# Sheet1.net
KiCad netlist of a schematic drawn in Altium Designer
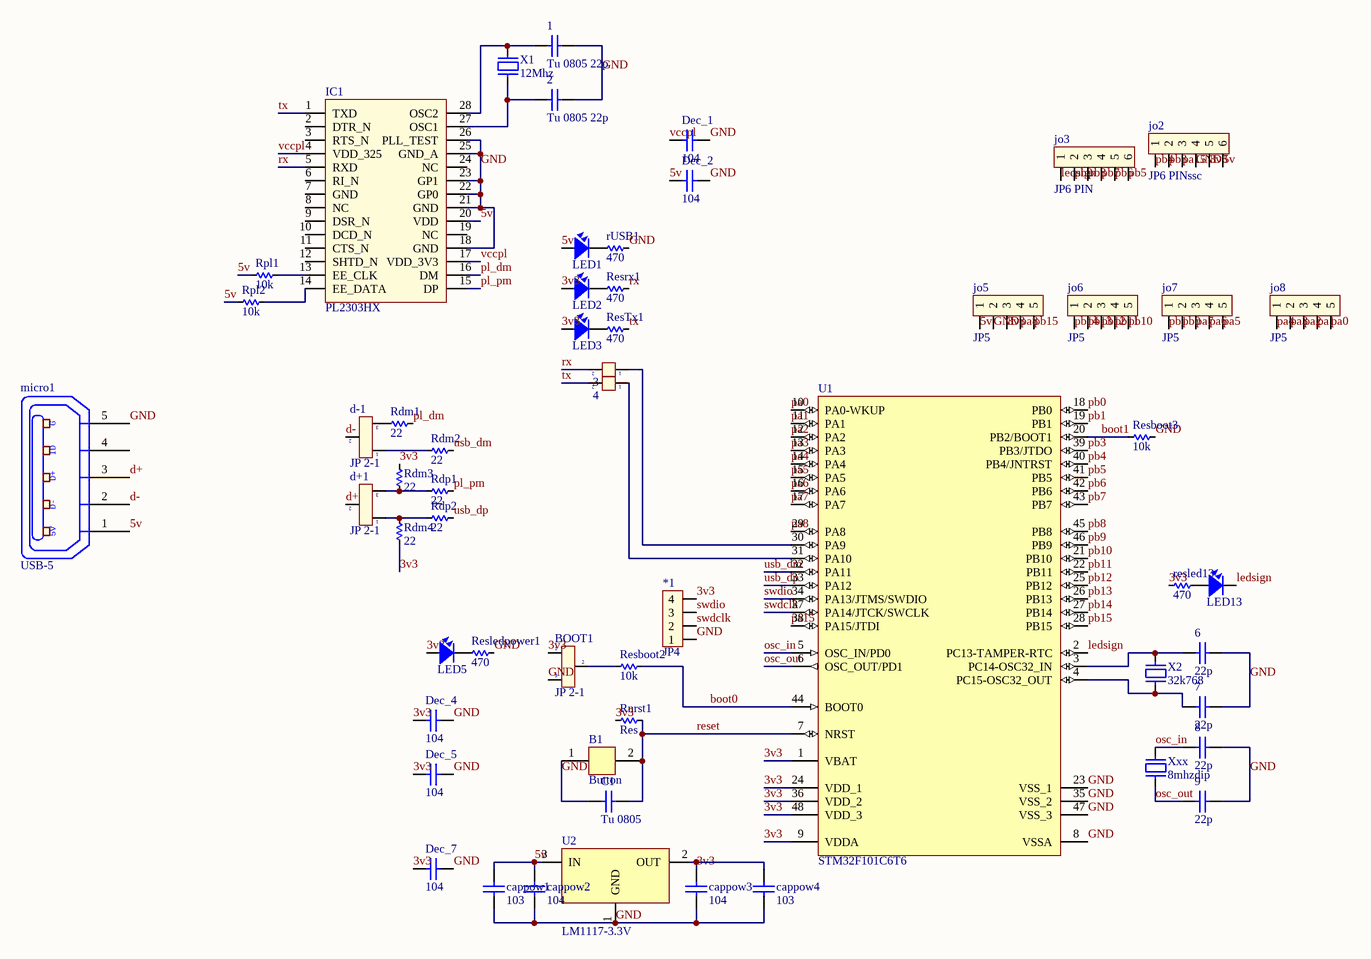
[diagram p0: Sheet1.SchDoc]

(export (version "E")
  (design (tool "Eeschema 10.0.6"))
  (components
    (comp (ref "*1")
      (value "JP4")
      (footprint "JP4")
      (libsource (lib "MH_THU VIEN CHUAN 12-03-2015") (part "JP4"))
    )
    (comp (ref "1")
      (value "Tu 0805 22p")
      (footprint "Tu 0805")
      (libsource (lib "MH_THU VIEN CHUAN 12-03-2015") (part "CAP 0805"))
    )
    (comp (ref "2")
      (value "Tu 0805 22p")
      (footprint "Tu 0805")
      (libsource (lib "MH_THU VIEN CHUAN 12-03-2015") (part "CAP 0805"))
    )
    (comp (ref "3")
      (value "Jumper 2")
      (footprint "JP2")
      (libsource (lib "MH_THU VIEN CHUAN 12-03-2015") (part "JP 2"))
    )
    (comp (ref "4")
      (value "Jumper 2")
      (footprint "JP2")
      (libsource (lib "MH_THU VIEN CHUAN 12-03-2015") (part "JP 2"))
    )
    (comp (ref "6")
      (value "22p")
      (footprint "Tu 0805")
      (libsource (lib "MH_THU VIEN CHUAN 12-03-2015") (part "CAP 0805"))
    )
    (comp (ref "7")
      (value "22p")
      (footprint "Tu 0805")
      (libsource (lib "MH_THU VIEN CHUAN 12-03-2015") (part "CAP 0805"))
    )
    (comp (ref "8")
      (value "22p")
      (footprint "Tu 0805")
      (libsource (lib "MH_THU VIEN CHUAN 12-03-2015") (part "CAP 0805"))
    )
    (comp (ref "9")
      (value "22p")
      (footprint "Tu 0805")
      (libsource (lib "MH_THU VIEN CHUAN 12-03-2015") (part "CAP 0805"))
    )
    (comp (ref "B1")
      (value "Button")
      (footprint "Button 2 Pin")
      (description "Button 2 pin")
      (libsource (lib "MH_THU VIEN CHUAN 12-03-2015") (part "Button 2 Pin"))
    )
    (comp (ref "BOOT1")
      (value "JP 2-1")
      (footprint "JP3")
      (description "Jumper 2-1")
      (libsource (lib "") (part "JP 2-1_1_1"))
    )
    (comp (ref "C1")
      (value "Tu 0805")
      (footprint "Tu 0805")
      (libsource (lib "MH_THU VIEN CHUAN 12-03-2015") (part "CAP 0805"))
    )
    (comp (ref "cappow1")
      (value "103")
      (footprint "Tu 0805")
      (libsource (lib "MH_THU VIEN CHUAN 12-03-2015") (part "CAP 0805"))
    )
    (comp (ref "cappow2")
      (value "104")
      (footprint "Tu 0805")
      (libsource (lib "MH_THU VIEN CHUAN 12-03-2015") (part "CAP 0805"))
    )
    (comp (ref "cappow3")
      (value "104")
      (footprint "Tu 0805")
      (libsource (lib "MH_THU VIEN CHUAN 12-03-2015") (part "CAP 0805"))
    )
    (comp (ref "cappow4")
      (value "103")
      (footprint "Tu 0805")
      (libsource (lib "MH_THU VIEN CHUAN 12-03-2015") (part "CAP 0805"))
    )
    (comp (ref "d+1")
      (value "JP 2-1")
      (footprint "JP3")
      (description "Jumper 2-1")
      (libsource (lib "MH_THU VIEN CHUAN 12-03-2015") (part "JP 2-1_1"))
    )
    (comp (ref "d-1")
      (value "JP 2-1")
      (footprint "JP3")
      (description "Jumper 2-1")
      (libsource (lib "MH_THU VIEN CHUAN 12-03-2015") (part "JP 2-1_1"))
    )
    (comp (ref "Dec_1")
      (value "104")
      (footprint "Tu 0805")
      (libsource (lib "MH_THU VIEN CHUAN 12-03-2015") (part "CAP 0805"))
    )
    (comp (ref "Dec_2")
      (value "104")
      (footprint "Tu 0805")
      (libsource (lib "MH_THU VIEN CHUAN 12-03-2015") (part "CAP 0805"))
    )
    (comp (ref "Dec_4")
      (value "104")
      (footprint "Tu 0805")
      (libsource (lib "MH_THU VIEN CHUAN 12-03-2015") (part "CAP 0805"))
    )
    (comp (ref "Dec_5")
      (value "104")
      (footprint "Tu 0805")
      (libsource (lib "MH_THU VIEN CHUAN 12-03-2015") (part "CAP 0805"))
    )
    (comp (ref "Dec_7")
      (value "104")
      (footprint "Tu 0805")
      (libsource (lib "MH_THU VIEN CHUAN 12-03-2015") (part "CAP 0805"))
    )
    (comp (ref "IC1")
      (value "PL2303HX")
      (footprint "SO-G28/C6.8")
      (description "USB - RS232 Converter")
      (libsource (lib "syhaunguyen") (part "PL2303HX"))
    )
    (comp (ref "jo2")
      (value "JP6 PINssc")
      (footprint "JP6")
      (description "JP6 PIN")
      (libsource (lib "MH_THU VIEN CHUAN 12-03-2015") (part "JP6"))
    )
    (comp (ref "jo3")
      (value "JP6 PIN")
      (footprint "JP6")
      (libsource (lib "MH_THU VIEN CHUAN 12-03-2015") (part "JP6"))
    )
    (comp (ref "jo5")
      (value "JP5")
      (footprint "JP5")
      (libsource (lib "MH_THU VIEN CHUAN 12-03-2015") (part "JP5"))
    )
    (comp (ref "jo6")
      (value "JP5")
      (footprint "JP5")
      (libsource (lib "MH_THU VIEN CHUAN 12-03-2015") (part "JP5"))
    )
    (comp (ref "jo7")
      (value "JP5")
      (footprint "JP5")
      (libsource (lib "MH_THU VIEN CHUAN 12-03-2015") (part "JP5"))
    )
    (comp (ref "jo8")
      (value "JP5")
      (footprint "JP5")
      (libsource (lib "MH_THU VIEN CHUAN 12-03-2015") (part "JP5"))
    )
    (comp (ref "LED1")
      (value "LED SMD")
      (footprint "SM-LED-0805-Blue")
      (libsource (lib "syhaunguyen") (part "LED-SMD-0805"))
    )
    (comp (ref "LED2")
      (value "LED SMD")
      (footprint "SM-LED-0805-Blue")
      (libsource (lib "syhaunguyen") (part "LED-SMD-0805"))
    )
    (comp (ref "LED3")
      (value "LED SMD")
      (footprint "SM-LED-0805-Blue")
      (libsource (lib "syhaunguyen") (part "LED-SMD-0805"))
    )
    (comp (ref "LED5")
      (value "LED SMD")
      (footprint "SM-LED-0805-Blue")
      (libsource (lib "syhaunguyen") (part "LED-SMD-0805"))
    )
    (comp (ref "LED13")
      (value "LED SMD")
      (footprint "SM-LED-0805-Blue")
      (libsource (lib "syhaunguyen") (part "LED-SMD-0805"))
    )
    (comp (ref "micro1")
      (value "USB-5")
      (footprint "USB-M1")
      (fields
        (field (name "MANUFACTURER") "FCI")
        (field (name "MANUFACTURER PART NUMBER") "10118193-0001LF")
        (field (name ".CREATOR") "MM")
        (field (name ".CHECKED PCB") "RF")
        (field (name ".CHECKED SCH") "MM")
      )
      (libsource (lib "LIBRARY") (part "USB-5"))
    )
    (comp (ref "Rdm1")
      (value "22")
      (footprint "RES-SMD-0805")
      (description "Resistor")
      (fields
        (field (name "MANUFACTURER") "Generic Components")
        (field (name "PUBLISHER") "Altium Hobart Technology Centre")
      )
      (libsource (lib "LIBRARY") (part "Res-SMD"))
    )
    (comp (ref "Rdm2")
      (value "22")
      (footprint "RES-SMD-0805")
      (description "Resistor")
      (fields
        (field (name "MANUFACTURER") "Generic Components")
        (field (name "PUBLISHER") "Altium Hobart Technology Centre")
      )
      (libsource (lib "LIBRARY") (part "Res-SMD"))
    )
    (comp (ref "Rdm3")
      (value "22")
      (footprint "RES-SMD-0805")
      (description "Resistor")
      (fields
        (field (name "MANUFACTURER") "Generic Components")
        (field (name "PUBLISHER") "Altium Hobart Technology Centre")
      )
      (libsource (lib "LIBRARY") (part "Res-SMD"))
    )
    (comp (ref "Rdm4")
      (value "22")
      (footprint "RES-SMD-0805")
      (description "Resistor")
      (fields
        (field (name "MANUFACTURER") "Generic Components")
        (field (name "PUBLISHER") "Altium Hobart Technology Centre")
      )
      (libsource (lib "LIBRARY") (part "Res-SMD"))
    )
    (comp (ref "Rdp1")
      (value "22")
      (footprint "RES-SMD-0805")
      (description "Resistor")
      (fields
        (field (name "MANUFACTURER") "Generic Components")
        (field (name "PUBLISHER") "Altium Hobart Technology Centre")
      )
      (libsource (lib "LIBRARY") (part "Res-SMD"))
    )
    (comp (ref "Rdp2")
      (value "22")
      (footprint "RES-SMD-0805")
      (description "Resistor")
      (fields
        (field (name "MANUFACTURER") "Generic Components")
        (field (name "PUBLISHER") "Altium Hobart Technology Centre")
      )
      (libsource (lib "LIBRARY") (part "Res-SMD"))
    )
    (comp (ref "Resboot2")
      (value "10k")
      (footprint "RES-SMD-0805")
      (description "Resistor")
      (fields
        (field (name "MANUFACTURER") "Generic Components")
        (field (name "PUBLISHER") "Altium Hobart Technology Centre")
      )
      (libsource (lib "LIBRARY") (part "Res-SMD"))
    )
    (comp (ref "Resboot3")
      (value "10k")
      (footprint "RES-SMD-0805")
      (description "Resistor")
      (fields
        (field (name "MANUFACTURER") "Generic Components")
        (field (name "PUBLISHER") "Altium Hobart Technology Centre")
      )
      (libsource (lib "LIBRARY") (part "Res-SMD"))
    )
    (comp (ref "resled13")
      (value "470")
      (footprint "RES-SMD-0805")
      (description "Resistor")
      (fields
        (field (name "MANUFACTURER") "Generic Components")
        (field (name "PUBLISHER") "Altium Hobart Technology Centre")
      )
      (libsource (lib "LIBRARY") (part "Res-SMD"))
    )
    (comp (ref "Resledpower1")
      (value "470")
      (footprint "RES-SMD-0805")
      (description "Resistor")
      (fields
        (field (name "MANUFACTURER") "Generic Components")
        (field (name "PUBLISHER") "Altium Hobart Technology Centre")
      )
      (libsource (lib "LIBRARY") (part "Res-SMD"))
    )
    (comp (ref "Resrx1")
      (value "470")
      (footprint "RES-SMD-0805")
      (description "Resistor")
      (fields
        (field (name "MANUFACTURER") "Generic Components")
        (field (name "PUBLISHER") "Altium Hobart Technology Centre")
      )
      (libsource (lib "LIBRARY") (part "Res-SMD"))
    )
    (comp (ref "ResTx1")
      (value "470")
      (footprint "RES-SMD-0805")
      (description "Resistor")
      (fields
        (field (name "MANUFACTURER") "Generic Components")
        (field (name "PUBLISHER") "Altium Hobart Technology Centre")
      )
      (libsource (lib "LIBRARY") (part "Res-SMD"))
    )
    (comp (ref "Rnrst1")
      (value "Res")
      (footprint "RES-SMD-0805")
      (description "Resistor")
      (fields
        (field (name "MANUFACTURER") "Generic Components")
        (field (name "PUBLISHER") "Altium Hobart Technology Centre")
      )
      (libsource (lib "LIBRARY") (part "Res-SMD"))
    )
    (comp (ref "Rpl1")
      (value "10k")
      (footprint "RES-SMD-0805")
      (description "Resistor")
      (fields
        (field (name "MANUFACTURER") "Generic Components")
        (field (name "PUBLISHER") "Altium Hobart Technology Centre")
      )
      (libsource (lib "LIBRARY") (part "Res-SMD"))
    )
    (comp (ref "Rpl2")
      (value "10k")
      (footprint "RES-SMD-0805")
      (description "Resistor")
      (fields
        (field (name "MANUFACTURER") "Generic Components")
        (field (name "PUBLISHER") "Altium Hobart Technology Centre")
      )
      (libsource (lib "LIBRARY") (part "Res-SMD"))
    )
    (comp (ref "rUSB1")
      (value "470")
      (footprint "RES-SMD-0805")
      (description "Resistor")
      (fields
        (field (name "MANUFACTURER") "Generic Components")
        (field (name "PUBLISHER") "Altium Hobart Technology Centre")
      )
      (libsource (lib "LIBRARY") (part "Res-SMD"))
    )
    (comp (ref "U1")
      (value "STM32F101C6T6")
      (footprint "TQFP48")
      (description "STM32 ARM-based 32-bit MCU with 32 Kbytes Flash, 48-pin LQFP, Industrial Temperature")
      (fields (field (name "PUBLISHER") "Altium Limited"))
      (libsource (lib "LIBRARY") (part "STM32F101C6T6"))
    )
    (comp (ref "U2")
      (value "LM1117-3.3V")
      (footprint "LM1117-SOP")
      (description "800mA Low-Dropout Linear Regulator")
      (fields (field (name "CREATOR") "Nguyen Ba Bien"))
      (libsource (lib "MH_THU VIEN CHUAN 12-03-2015") (part "LM1117"))
    )
    (comp (ref "X1")
      (value "12Mhz")
      (footprint "XT2-SMD")
      (description "Crystal, 32.768 KHz, -40 to 85 degC, 3.2 x 1.5 x 0.9 mm SMD")
      (libsource (lib "LIBRARY") (part "XT2"))
    )
    (comp (ref "X2")
      (value "32k768")
      (footprint "XT32k")
      (description "Crystal, 32.768 KHz, -40 to 85 degC, 3.2 x 1.5 x 0.9 mm SMD")
      (libsource (lib "") (part "XT2_1"))
    )
    (comp (ref "Xxx")
      (value "8mhzdip")
      (footprint "XT2")
      (description "Crystal For all Crystal 2pin.")
      (libsource (lib "syhaunguyen") (part "XT2"))
    )
  )
  (nets
    (net (code "1") (name "/3v3") (class "Default")
      (node (ref "*1") (pin "4") (pinfunction "4_4") (pintype "passive"))
      (node (ref "BOOT1") (pin "1") (pinfunction "1_1") (pintype "passive"))
      (node (ref "Dec_4") (pin "1") (pinfunction "1_1") (pintype "passive"))
      (node (ref "Dec_5") (pin "1") (pinfunction "1_1") (pintype "passive"))
      (node (ref "Dec_7") (pin "1") (pinfunction "1_1") (pintype "passive"))
      (node (ref "LED2") (pin "1") (pinfunction "1_1") (pintype "passive"))
      (node (ref "LED3") (pin "1") (pinfunction "1_1") (pintype "passive"))
      (node (ref "LED5") (pin "1") (pinfunction "1_1") (pintype "passive"))
      (node (ref "Rdm3") (pin "1") (pinfunction "1_1") (pintype "passive"))
      (node (ref "Rdm4") (pin "2") (pinfunction "2_2") (pintype "passive"))
      (node (ref "Rnrst1") (pin "2") (pinfunction "2_2") (pintype "passive"))
      (node (ref "U1") (pin "1") (pinfunction "VBAT_1") (pintype "power_in"))
      (node (ref "U1") (pin "24") (pinfunction "VDD_1_24") (pintype "power_in"))
      (node (ref "U1") (pin "36") (pinfunction "VDD_2_36") (pintype "power_in"))
      (node (ref "U1") (pin "48") (pinfunction "VDD_3_48") (pintype "power_in"))
      (node (ref "U1") (pin "9") (pinfunction "VDDA_9") (pintype "power_in"))
      (node (ref "U2") (pin "2") (pinfunction "OUT_2") (pintype "passive"))
      (node (ref "cappow3") (pin "2") (pinfunction "2_2") (pintype "passive"))
      (node (ref "cappow4") (pin "2") (pinfunction "2_2") (pintype "passive"))
      (node (ref "jo2") (pin "5") (pinfunction "5_5") (pintype "passive"))
      (node (ref "jo5") (pin "3") (pinfunction "3_3") (pintype "passive"))
      (node (ref "resled13") (pin "2") (pinfunction "2_2") (pintype "passive"))
    )
    (net (code "2") (name "/5v") (class "Default")
      (node (ref "Dec_2") (pin "1") (pinfunction "1_1") (pintype "passive"))
      (node (ref "IC1") (pin "20") (pinfunction "VDD_20") (pintype "passive"))
      (node (ref "LED1") (pin "1") (pinfunction "1_1") (pintype "passive"))
      (node (ref "Rpl1") (pin "2") (pinfunction "2_2") (pintype "passive"))
      (node (ref "Rpl2") (pin "2") (pinfunction "2_2") (pintype "passive"))
      (node (ref "U2") (pin "3") (pinfunction "IN_3") (pintype "passive"))
      (node (ref "cappow1") (pin "2") (pinfunction "2_2") (pintype "passive"))
      (node (ref "cappow2") (pin "2") (pinfunction "2_2") (pintype "passive"))
      (node (ref "jo2") (pin "6") (pinfunction "6_6") (pintype "passive"))
      (node (ref "jo5") (pin "1") (pinfunction "1_1") (pintype "passive"))
      (node (ref "micro1") (pin "1") (pinfunction "P1_1") (pintype "passive"))
    )
    (net (code "3") (name "/GND") (class "Default")
      (node (ref "*1") (pin "1") (pinfunction "1_1") (pintype "passive"))
      (node (ref "1") (pin "2") (pinfunction "2_2") (pintype "passive"))
      (node (ref "2") (pin "2") (pinfunction "2_2") (pintype "passive"))
      (node (ref "6") (pin "2") (pinfunction "2_2") (pintype "passive"))
      (node (ref "7") (pin "2") (pinfunction "2_2") (pintype "passive"))
      (node (ref "8") (pin "2") (pinfunction "2_2") (pintype "passive"))
      (node (ref "9") (pin "2") (pinfunction "2_2") (pintype "passive"))
      (node (ref "B1") (pin "1") (pinfunction "1_1") (pintype "passive"))
      (node (ref "BOOT1") (pin "3") (pinfunction "3_3") (pintype "passive"))
      (node (ref "C1") (pin "2") (pinfunction "2_2") (pintype "passive"))
      (node (ref "Dec_1") (pin "1") (pinfunction "1_1") (pintype "passive"))
      (node (ref "Dec_2") (pin "2") (pinfunction "2_2") (pintype "passive"))
      (node (ref "Dec_4") (pin "2") (pinfunction "2_2") (pintype "passive"))
      (node (ref "Dec_5") (pin "2") (pinfunction "2_2") (pintype "passive"))
      (node (ref "Dec_7") (pin "2") (pinfunction "2_2") (pintype "passive"))
      (node (ref "IC1") (pin "18") (pinfunction "GND_18") (pintype "passive"))
      (node (ref "IC1") (pin "21") (pinfunction "GND_21") (pintype "passive"))
      (node (ref "IC1") (pin "22") (pinfunction "GP0_22") (pintype "passive"))
      (node (ref "IC1") (pin "23") (pinfunction "GP1_23") (pintype "passive"))
      (node (ref "IC1") (pin "25") (pinfunction "GND_A_25") (pintype "passive"))
      (node (ref "IC1") (pin "26") (pinfunction "PLL_TEST_26") (pintype "passive"))
      (node (ref "Resboot3") (pin "1") (pinfunction "1_1") (pintype "passive"))
      (node (ref "Resledpower1") (pin "1") (pinfunction "1_1") (pintype "passive"))
      (node (ref "U1") (pin "23") (pinfunction "VSS_1_23") (pintype "power_in"))
      (node (ref "U1") (pin "35") (pinfunction "VSS_2_35") (pintype "power_in"))
      (node (ref "U1") (pin "47") (pinfunction "VSS_3_47") (pintype "power_in"))
      (node (ref "U1") (pin "8") (pinfunction "VSSA_8") (pintype "power_in"))
      (node (ref "U2") (pin "1") (pinfunction "GND_1") (pintype "passive"))
      (node (ref "cappow1") (pin "1") (pinfunction "1_1") (pintype "passive"))
      (node (ref "cappow2") (pin "1") (pinfunction "1_1") (pintype "passive"))
      (node (ref "cappow3") (pin "1") (pinfunction "1_1") (pintype "passive"))
      (node (ref "cappow4") (pin "1") (pinfunction "1_1") (pintype "passive"))
      (node (ref "jo2") (pin "4") (pinfunction "4_4") (pintype "passive"))
      (node (ref "jo5") (pin "2") (pinfunction "2_2") (pintype "passive"))
      (node (ref "micro1") (pin "5") (pinfunction "P5_5") (pintype "passive"))
      (node (ref "rUSB1") (pin "1") (pinfunction "1_1") (pintype "passive"))
    )
    (net (code "4") (name "/boot0") (class "Default")
      (node (ref "Resboot2") (pin "1") (pinfunction "1_1") (pintype "passive"))
      (node (ref "U1") (pin "44") (pinfunction "BOOT0_44") (pintype "input"))
    )
    (net (code "5") (name "/boot1") (class "Default")
      (node (ref "Resboot3") (pin "2") (pinfunction "2_2") (pintype "passive"))
      (node (ref "U1") (pin "20") (pinfunction "PB2/BOOT1_20") (pintype "bidirectional"))
    )
    (net (code "6") (name "/d+") (class "Default")
      (node (ref "d+1") (pin "2") (pinfunction "2_2") (pintype "passive"))
      (node (ref "micro1") (pin "3") (pinfunction "P3_3") (pintype "passive"))
    )
    (net (code "7") (name "/d-") (class "Default")
      (node (ref "d-1") (pin "2") (pinfunction "2_2") (pintype "passive"))
      (node (ref "micro1") (pin "2") (pinfunction "P2_2") (pintype "passive"))
    )
    (net (code "8") (name "/ledsign") (class "Default")
      (node (ref "LED13") (pin "2") (pinfunction "2_2") (pintype "passive"))
      (node (ref "U1") (pin "2") (pinfunction "PC13-TAMPER-RTC_2") (pintype "bidirectional"))
      (node (ref "jo3") (pin "1") (pinfunction "1_1") (pintype "passive"))
    )
    (net (code "9") (name "/osc_in") (class "Default")
      (node (ref "8") (pin "1") (pinfunction "1_1") (pintype "passive"))
      (node (ref "U1") (pin "5") (pinfunction "OSC_IN/PD0_5") (pintype "input"))
      (node (ref "Xxx") (pin "2") (pinfunction "2_2") (pintype "passive"))
    )
    (net (code "10") (name "/osc_out") (class "Default")
      (node (ref "9") (pin "1") (pinfunction "1_1") (pintype "passive"))
      (node (ref "U1") (pin "6") (pinfunction "OSC_OUT/PD1_6") (pintype "output"))
      (node (ref "Xxx") (pin "1") (pinfunction "1_1") (pintype "passive"))
    )
    (net (code "11") (name "/pa0") (class "Default")
      (node (ref "U1") (pin "10") (pinfunction "PA0-WKUP_10") (pintype "bidirectional"))
      (node (ref "jo8") (pin "5") (pinfunction "5_5") (pintype "passive"))
    )
    (net (code "12") (name "/pa1") (class "Default")
      (node (ref "U1") (pin "11") (pinfunction "PA1_11") (pintype "bidirectional"))
      (node (ref "jo8") (pin "4") (pinfunction "4_4") (pintype "passive"))
    )
    (net (code "13") (name "/pa2") (class "Default")
      (node (ref "U1") (pin "12") (pinfunction "PA2_12") (pintype "bidirectional"))
      (node (ref "jo8") (pin "3") (pinfunction "3_3") (pintype "passive"))
    )
    (net (code "14") (name "/pa3") (class "Default")
      (node (ref "U1") (pin "13") (pinfunction "PA3_13") (pintype "bidirectional"))
      (node (ref "jo8") (pin "2") (pinfunction "2_2") (pintype "passive"))
    )
    (net (code "15") (name "/pa4") (class "Default")
      (node (ref "U1") (pin "14") (pinfunction "PA4_14") (pintype "bidirectional"))
      (node (ref "jo8") (pin "1") (pinfunction "1_1") (pintype "passive"))
    )
    (net (code "16") (name "/pa5") (class "Default")
      (node (ref "U1") (pin "15") (pinfunction "PA5_15") (pintype "bidirectional"))
      (node (ref "jo7") (pin "5") (pinfunction "5_5") (pintype "passive"))
    )
    (net (code "17") (name "/pa6") (class "Default")
      (node (ref "U1") (pin "16") (pinfunction "PA6_16") (pintype "bidirectional"))
      (node (ref "jo7") (pin "4") (pinfunction "4_4") (pintype "passive"))
    )
    (net (code "18") (name "/pa7") (class "Default")
      (node (ref "U1") (pin "17") (pinfunction "PA7_17") (pintype "bidirectional"))
      (node (ref "jo7") (pin "3") (pinfunction "3_3") (pintype "passive"))
    )
    (net (code "19") (name "/pa8") (class "Default")
      (node (ref "U1") (pin "29") (pinfunction "PA8_29") (pintype "bidirectional"))
      (node (ref "jo5") (pin "4") (pinfunction "4_4") (pintype "passive"))
    )
    (net (code "20") (name "/pa15") (class "Default")
      (node (ref "U1") (pin "38") (pinfunction "PA15/JTDI_38") (pintype "bidirectional"))
      (node (ref "jo2") (pin "3") (pinfunction "3_3") (pintype "passive"))
    )
    (net (code "21") (name "/pb0") (class "Default")
      (node (ref "U1") (pin "18") (pinfunction "PB0_18") (pintype "bidirectional"))
      (node (ref "jo7") (pin "2") (pinfunction "2_2") (pintype "passive"))
    )
    (net (code "22") (name "/pb1") (class "Default")
      (node (ref "U1") (pin "19") (pinfunction "PB1_19") (pintype "bidirectional"))
      (node (ref "jo7") (pin "1") (pinfunction "1_1") (pintype "passive"))
    )
    (net (code "23") (name "/pb3") (class "Default")
      (node (ref "U1") (pin "39") (pinfunction "PB3/JTDO_39") (pintype "bidirectional"))
      (node (ref "jo2") (pin "2") (pinfunction "2_2") (pintype "passive"))
    )
    (net (code "24") (name "/pb4") (class "Default")
      (node (ref "U1") (pin "40") (pinfunction "PB4/JNTRST_40") (pintype "bidirectional"))
      (node (ref "jo2") (pin "1") (pinfunction "1_1") (pintype "passive"))
    )
    (net (code "25") (name "/pb5") (class "Default")
      (node (ref "U1") (pin "41") (pinfunction "PB5_41") (pintype "bidirectional"))
      (node (ref "jo3") (pin "6") (pinfunction "6_6") (pintype "passive"))
    )
    (net (code "26") (name "/pb6") (class "Default")
      (node (ref "U1") (pin "42") (pinfunction "PB6_42") (pintype "bidirectional"))
      (node (ref "jo3") (pin "5") (pinfunction "5_5") (pintype "passive"))
    )
    (net (code "27") (name "/pb7") (class "Default")
      (node (ref "U1") (pin "43") (pinfunction "PB7_43") (pintype "bidirectional"))
      (node (ref "jo3") (pin "4") (pinfunction "4_4") (pintype "passive"))
    )
    (net (code "28") (name "/pb8") (class "Default")
      (node (ref "U1") (pin "45") (pinfunction "PB8_45") (pintype "bidirectional"))
      (node (ref "jo3") (pin "3") (pinfunction "3_3") (pintype "passive"))
    )
    (net (code "29") (name "/pb9") (class "Default")
      (node (ref "U1") (pin "46") (pinfunction "PB9_46") (pintype "bidirectional"))
      (node (ref "jo3") (pin "2") (pinfunction "2_2") (pintype "passive"))
    )
    (net (code "30") (name "/pb10") (class "Default")
      (node (ref "U1") (pin "21") (pinfunction "PB10_21") (pintype "bidirectional"))
      (node (ref "jo6") (pin "5") (pinfunction "5_5") (pintype "passive"))
    )
    (net (code "31") (name "/pb11") (class "Default")
      (node (ref "U1") (pin "22") (pinfunction "PB11_22") (pintype "bidirectional"))
      (node (ref "jo6") (pin "4") (pinfunction "4_4") (pintype "passive"))
    )
    (net (code "32") (name "/pb12") (class "Default")
      (node (ref "U1") (pin "25") (pinfunction "PB12_25") (pintype "bidirectional"))
      (node (ref "jo6") (pin "3") (pinfunction "3_3") (pintype "passive"))
    )
    (net (code "33") (name "/pb13") (class "Default")
      (node (ref "U1") (pin "26") (pinfunction "PB13_26") (pintype "bidirectional"))
      (node (ref "jo6") (pin "2") (pinfunction "2_2") (pintype "passive"))
    )
    (net (code "34") (name "/pb14") (class "Default")
      (node (ref "U1") (pin "27") (pinfunction "PB14_27") (pintype "bidirectional"))
      (node (ref "jo6") (pin "1") (pinfunction "1_1") (pintype "passive"))
    )
    (net (code "35") (name "/pb15") (class "Default")
      (node (ref "U1") (pin "28") (pinfunction "PB15_28") (pintype "bidirectional"))
      (node (ref "jo5") (pin "5") (pinfunction "5_5") (pintype "passive"))
    )
    (net (code "36") (name "/pl_dm") (class "Default")
      (node (ref "IC1") (pin "16") (pinfunction "DM_16") (pintype "passive"))
      (node (ref "Rdm1") (pin "1") (pinfunction "1_1") (pintype "passive"))
    )
    (net (code "37") (name "/pl_pm") (class "Default")
      (node (ref "IC1") (pin "15") (pinfunction "DP_15") (pintype "passive"))
      (node (ref "Rdp1") (pin "1") (pinfunction "1_1") (pintype "passive"))
    )
    (net (code "38") (name "/reset") (class "Default")
      (node (ref "B1") (pin "2") (pinfunction "2_2") (pintype "passive"))
      (node (ref "C1") (pin "1") (pinfunction "1_1") (pintype "passive"))
      (node (ref "Rnrst1") (pin "1") (pinfunction "1_1") (pintype "passive"))
      (node (ref "U1") (pin "7") (pinfunction "NRST_7") (pintype "bidirectional"))
    )
    (net (code "39") (name "/rx") (class "Default")
      (node (ref "3") (pin "2") (pinfunction "2_2") (pintype "passive"))
      (node (ref "IC1") (pin "5") (pinfunction "RXD_5") (pintype "passive"))
      (node (ref "Resrx1") (pin "1") (pinfunction "1_1") (pintype "passive"))
    )
    (net (code "40") (name "/swdclk") (class "Default")
      (node (ref "*1") (pin "2") (pinfunction "2_2") (pintype "passive"))
      (node (ref "U1") (pin "37") (pinfunction "PA14/JTCK/SWCLK_37") (pintype "bidirectional"))
    )
    (net (code "41") (name "/swdio") (class "Default")
      (node (ref "*1") (pin "3") (pinfunction "3_3") (pintype "passive"))
      (node (ref "U1") (pin "34") (pinfunction "PA13/JTMS/SWDIO_34") (pintype "bidirectional"))
    )
    (net (code "42") (name "/tx") (class "Default")
      (node (ref "4") (pin "2") (pinfunction "2_2") (pintype "passive"))
      (node (ref "IC1") (pin "1") (pinfunction "TXD_1") (pintype "passive"))
      (node (ref "ResTx1") (pin "1") (pinfunction "1_1") (pintype "passive"))
    )
    (net (code "43") (name "/usb_dm") (class "Default")
      (node (ref "Rdm2") (pin "1") (pinfunction "1_1") (pintype "passive"))
      (node (ref "U1") (pin "32") (pinfunction "PA11_32") (pintype "bidirectional"))
    )
    (net (code "44") (name "/usb_dp") (class "Default")
      (node (ref "Rdp2") (pin "1") (pinfunction "1_1") (pintype "passive"))
      (node (ref "U1") (pin "33") (pinfunction "PA12_33") (pintype "bidirectional"))
    )
    (net (code "45") (name "/vccpl") (class "Default")
      (node (ref "Dec_1") (pin "2") (pinfunction "2_2") (pintype "passive"))
      (node (ref "IC1") (pin "17") (pinfunction "VDD_3V3_17") (pintype "passive"))
      (node (ref "IC1") (pin "4") (pinfunction "VDD_325_4") (pintype "passive"))
    )
    (net (code "46") (name "Net-(BOOT1-Pad2)") (class "Default")
      (node (ref "BOOT1") (pin "2") (pinfunction "2_2") (pintype "passive"))
      (node (ref "Resboot2") (pin "2") (pinfunction "2_2") (pintype "passive"))
    )
    (net (code "47") (name "Net-(IC1-EE_CLK)") (class "Default")
      (node (ref "IC1") (pin "13") (pinfunction "EE_CLK_13") (pintype "passive"))
      (node (ref "Rpl1") (pin "1") (pinfunction "1_1") (pintype "passive"))
    )
    (net (code "48") (name "Net-(IC1-EE_DATA)") (class "Default")
      (node (ref "IC1") (pin "14") (pinfunction "EE_DATA_14") (pintype "passive"))
      (node (ref "Rpl2") (pin "1") (pinfunction "1_1") (pintype "passive"))
    )
    (net (code "49") (name "Net-(IC1-OSC1)") (class "Default")
      (node (ref "2") (pin "1") (pinfunction "1_1") (pintype "passive"))
      (node (ref "IC1") (pin "27") (pinfunction "OSC1_27") (pintype "passive"))
      (node (ref "X1") (pin "1") (pinfunction "1_1") (pintype "passive"))
    )
    (net (code "50") (name "Net-(IC1-OSC2)") (class "Default")
      (node (ref "1") (pin "1") (pinfunction "1_1") (pintype "passive"))
      (node (ref "IC1") (pin "28") (pinfunction "OSC2_28") (pintype "passive"))
      (node (ref "X1") (pin "2") (pinfunction "2_2") (pintype "passive"))
    )
    (net (code "51") (name "Net-(LED1-Pad2)") (class "Default")
      (node (ref "LED1") (pin "2") (pinfunction "2_2") (pintype "passive"))
      (node (ref "rUSB1") (pin "2") (pinfunction "2_2") (pintype "passive"))
    )
    (net (code "52") (name "Net-(LED2-Pad2)") (class "Default")
      (node (ref "LED2") (pin "2") (pinfunction "2_2") (pintype "passive"))
      (node (ref "Resrx1") (pin "2") (pinfunction "2_2") (pintype "passive"))
    )
    (net (code "53") (name "Net-(LED3-Pad2)") (class "Default")
      (node (ref "LED3") (pin "2") (pinfunction "2_2") (pintype "passive"))
      (node (ref "ResTx1") (pin "2") (pinfunction "2_2") (pintype "passive"))
    )
    (net (code "54") (name "Net-(LED5-Pad2)") (class "Default")
      (node (ref "LED5") (pin "2") (pinfunction "2_2") (pintype "passive"))
      (node (ref "Resledpower1") (pin "2") (pinfunction "2_2") (pintype "passive"))
    )
    (net (code "55") (name "Net-(LED13-Pad1)") (class "Default")
      (node (ref "LED13") (pin "1") (pinfunction "1_1") (pintype "passive"))
      (node (ref "resled13") (pin "1") (pinfunction "1_1") (pintype "passive"))
    )
    (net (code "56") (name "Net-(Rdm1-Pad2)") (class "Default")
      (node (ref "Rdm1") (pin "2") (pinfunction "2_2") (pintype "passive"))
      (node (ref "d-1") (pin "3") (pinfunction "3_3") (pintype "passive"))
    )
    (net (code "57") (name "Net-(Rdm2-Pad2)") (class "Default")
      (node (ref "Rdm2") (pin "2") (pinfunction "2_2") (pintype "passive"))
      (node (ref "d-1") (pin "1") (pinfunction "1_1") (pintype "passive"))
    )
    (net (code "58") (name "Net-(Rdm3-Pad2)") (class "Default")
      (node (ref "Rdm3") (pin "2") (pinfunction "2_2") (pintype "passive"))
      (node (ref "Rdp1") (pin "2") (pinfunction "2_2") (pintype "passive"))
      (node (ref "d+1") (pin "3") (pinfunction "3_3") (pintype "passive"))
    )
    (net (code "59") (name "Net-(Rdm4-Pad1)") (class "Default")
      (node (ref "Rdm4") (pin "1") (pinfunction "1_1") (pintype "passive"))
      (node (ref "Rdp2") (pin "2") (pinfunction "2_2") (pintype "passive"))
      (node (ref "d+1") (pin "1") (pinfunction "1_1") (pintype "passive"))
    )
    (net (code "60") (name "Net-(U1-PA9)") (class "Default")
      (node (ref "3") (pin "1") (pinfunction "1_1") (pintype "passive"))
      (node (ref "U1") (pin "30") (pinfunction "PA9_30") (pintype "bidirectional"))
    )
    (net (code "61") (name "Net-(U1-PA10)") (class "Default")
      (node (ref "4") (pin "1") (pinfunction "1_1") (pintype "passive"))
      (node (ref "U1") (pin "31") (pinfunction "PA10_31") (pintype "bidirectional"))
    )
    (net (code "62") (name "Net-(U1-PC14-OSC32_IN)") (class "Default")
      (node (ref "6") (pin "1") (pinfunction "1_1") (pintype "passive"))
      (node (ref "U1") (pin "3") (pinfunction "PC14-OSC32_IN_3") (pintype "bidirectional"))
      (node (ref "X2") (pin "1") (pinfunction "1_1") (pintype "passive"))
    )
    (net (code "63") (name "Net-(U1-PC15-OSC32_OUT)") (class "Default")
      (node (ref "7") (pin "1") (pinfunction "1_1") (pintype "passive"))
      (node (ref "U1") (pin "4") (pinfunction "PC15-OSC32_OUT_4") (pintype "bidirectional"))
      (node (ref "X2") (pin "2") (pinfunction "2_2") (pintype "passive"))
    )
    (net (code "64") (name "unconnected-(IC1-CTS_N-Pad11)") (class "Default")
      (node (ref "IC1") (pin "11") (pinfunction "CTS_N_11") (pintype "passive"))
    )
    (net (code "65") (name "unconnected-(IC1-DCD_N-Pad10)") (class "Default")
      (node (ref "IC1") (pin "10") (pinfunction "DCD_N_10") (pintype "passive"))
    )
    (net (code "66") (name "unconnected-(IC1-DSR_N-Pad9)") (class "Default")
      (node (ref "IC1") (pin "9") (pinfunction "DSR_N_9") (pintype "passive"))
    )
    (net (code "67") (name "unconnected-(IC1-DTR_N-Pad2)") (class "Default")
      (node (ref "IC1") (pin "2") (pinfunction "DTR_N_2") (pintype "passive"))
    )
    (net (code "68") (name "unconnected-(IC1-GND-Pad7)") (class "Default")
      (node (ref "IC1") (pin "7") (pinfunction "GND_7") (pintype "passive"))
    )
    (net (code "69") (name "unconnected-(IC1-NC-Pad8)") (class "Default")
      (node (ref "IC1") (pin "8") (pinfunction "NC_8") (pintype "passive"))
    )
    (net (code "70") (name "unconnected-(IC1-NC-Pad19)") (class "Default")
      (node (ref "IC1") (pin "19") (pinfunction "NC_19") (pintype "passive"))
    )
    (net (code "71") (name "unconnected-(IC1-NC-Pad24)") (class "Default")
      (node (ref "IC1") (pin "24") (pinfunction "NC_24") (pintype "passive"))
    )
    (net (code "72") (name "unconnected-(IC1-RI_N-Pad6)") (class "Default")
      (node (ref "IC1") (pin "6") (pinfunction "RI_N_6") (pintype "passive"))
    )
    (net (code "73") (name "unconnected-(IC1-RTS_N-Pad3)") (class "Default")
      (node (ref "IC1") (pin "3") (pinfunction "RTS_N_3") (pintype "passive"))
    )
    (net (code "74") (name "unconnected-(IC1-SHTD_N-Pad12)") (class "Default")
      (node (ref "IC1") (pin "12") (pinfunction "SHTD_N_12") (pintype "passive"))
    )
    (net (code "75") (name "unconnected-(micro1-P4-Pad4)") (class "Default")
      (node (ref "micro1") (pin "4") (pinfunction "P4_4") (pintype "passive"))
    )
  )
)
